# Power.net
KiCad netlist of a schematic drawn in Altium Designer
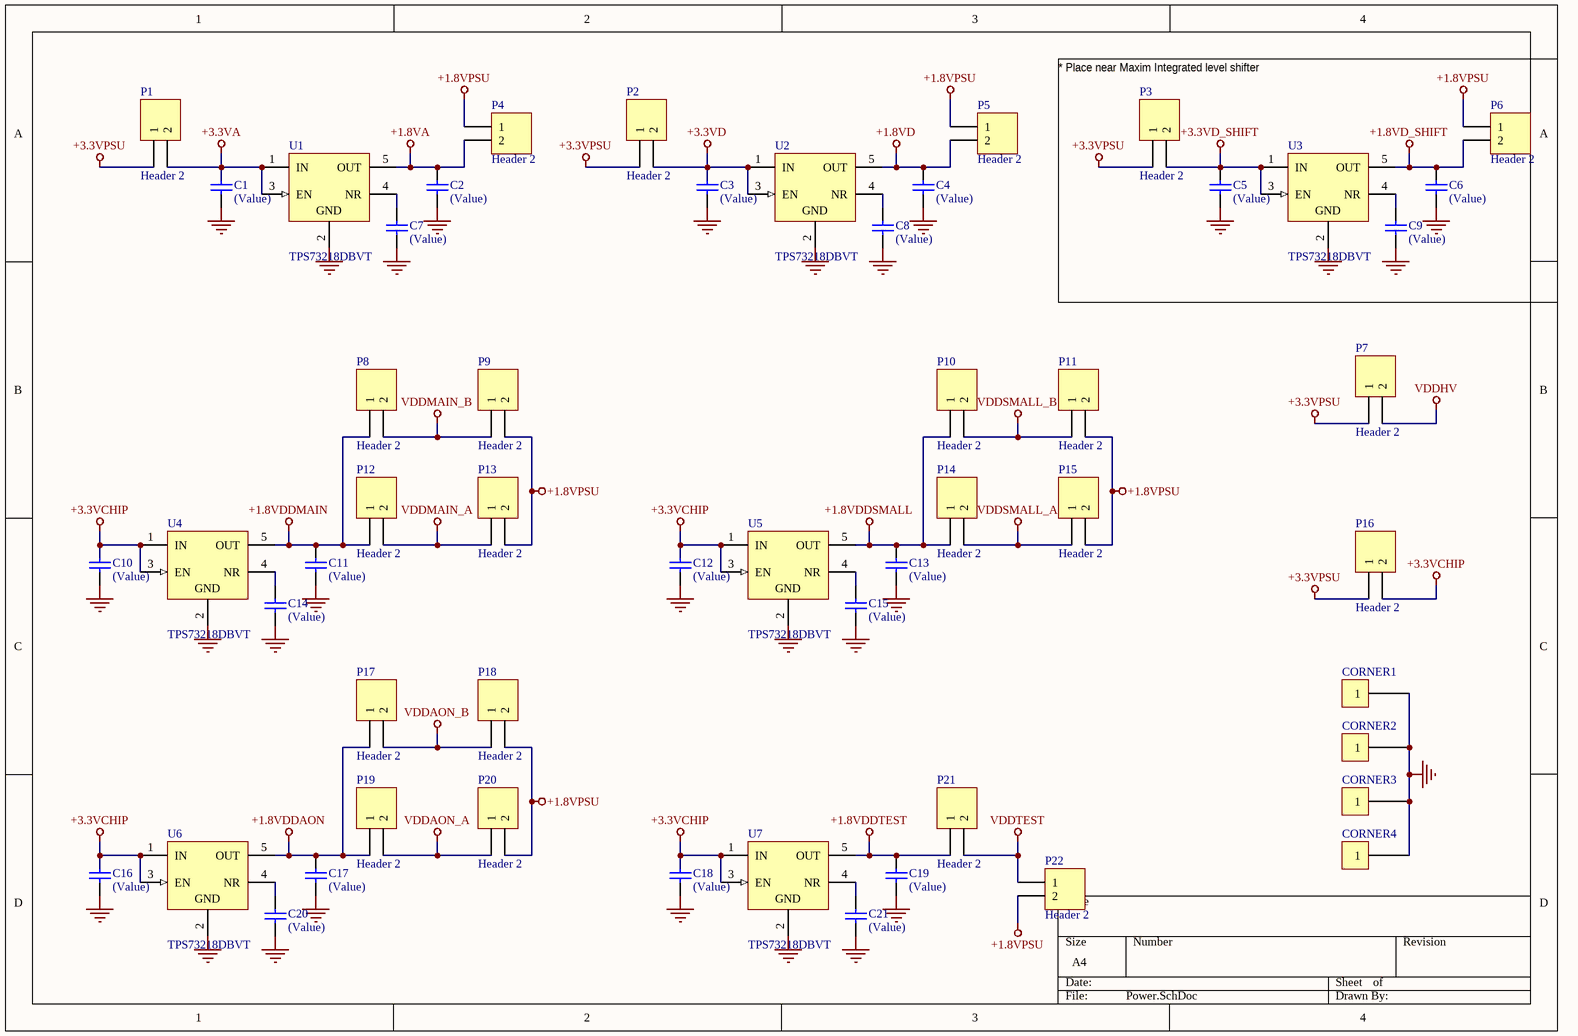
[diagram p0: Power.SchDoc]

(export (version "E")
  (design (tool "Eeschema 10.0.6"))
  (components
    (comp (ref "C1")
      (value "(Value)")
      (footprint "CAPC1608X90X35ML10T15")
      (description "0603")
      (fields (field (name "MANUFACTURER") "Murata"))
      (libsource (lib "Altium Content Vault") (part "CAP-NP-2"))
    )
    (comp (ref "C2")
      (value "(Value)")
      (footprint "CAPC1608X90X35ML10T15")
      (description "0603")
      (fields (field (name "MANUFACTURER") "Murata"))
      (libsource (lib "Altium Content Vault") (part "CAP-NP-2"))
    )
    (comp (ref "C3")
      (value "(Value)")
      (footprint "CAPC1608X90X35ML10T15")
      (description "0603")
      (fields (field (name "MANUFACTURER") "Murata"))
      (libsource (lib "Altium Content Vault") (part "CAP-NP-2"))
    )
    (comp (ref "C4")
      (value "(Value)")
      (footprint "CAPC1608X90X35ML10T15")
      (description "0603")
      (fields (field (name "MANUFACTURER") "Murata"))
      (libsource (lib "Altium Content Vault") (part "CAP-NP-2"))
    )
    (comp (ref "C5")
      (value "(Value)")
      (footprint "CAPC1608X90X35ML10T15")
      (description "0603")
      (fields (field (name "MANUFACTURER") "Murata"))
      (libsource (lib "Altium Content Vault") (part "CAP-NP-2"))
    )
    (comp (ref "C6")
      (value "(Value)")
      (footprint "CAPC1608X90X35ML10T15")
      (description "0603")
      (fields (field (name "MANUFACTURER") "Murata"))
      (libsource (lib "Altium Content Vault") (part "CAP-NP-2"))
    )
    (comp (ref "C7")
      (value "(Value)")
      (footprint "CAPC1608X90X35ML10T15")
      (description "0603")
      (fields (field (name "MANUFACTURER") "Murata"))
      (libsource (lib "Altium Content Vault") (part "CAP-NP-2"))
    )
    (comp (ref "C8")
      (value "(Value)")
      (footprint "CAPC1608X90X35ML10T15")
      (description "0603")
      (fields (field (name "MANUFACTURER") "Murata"))
      (libsource (lib "Altium Content Vault") (part "CAP-NP-2"))
    )
    (comp (ref "C9")
      (value "(Value)")
      (footprint "CAPC1608X90X35ML10T15")
      (description "0603")
      (fields (field (name "MANUFACTURER") "Murata"))
      (libsource (lib "Altium Content Vault") (part "CAP-NP-2"))
    )
    (comp (ref "C10")
      (value "(Value)")
      (footprint "CAPC1608X90X35ML10T15")
      (description "0603")
      (fields (field (name "MANUFACTURER") "Murata"))
      (libsource (lib "Altium Content Vault") (part "CAP-NP-2"))
    )
    (comp (ref "C11")
      (value "(Value)")
      (footprint "CAPC1608X90X35ML10T15")
      (description "0603")
      (fields (field (name "MANUFACTURER") "Murata"))
      (libsource (lib "Altium Content Vault") (part "CAP-NP-2"))
    )
    (comp (ref "C12")
      (value "(Value)")
      (footprint "CAPC1608X90X35ML10T15")
      (description "0603")
      (fields (field (name "MANUFACTURER") "Murata"))
      (libsource (lib "Altium Content Vault") (part "CAP-NP-2"))
    )
    (comp (ref "C13")
      (value "(Value)")
      (footprint "CAPC1608X90X35ML10T15")
      (description "0603")
      (fields (field (name "MANUFACTURER") "Murata"))
      (libsource (lib "Altium Content Vault") (part "CAP-NP-2"))
    )
    (comp (ref "C14")
      (value "(Value)")
      (footprint "CAPC1608X90X35ML10T15")
      (description "0603")
      (fields (field (name "MANUFACTURER") "Murata"))
      (libsource (lib "Altium Content Vault") (part "CAP-NP-2"))
    )
    (comp (ref "C15")
      (value "(Value)")
      (footprint "CAPC1608X90X35ML10T15")
      (description "0603")
      (fields (field (name "MANUFACTURER") "Murata"))
      (libsource (lib "Altium Content Vault") (part "CAP-NP-2"))
    )
    (comp (ref "C16")
      (value "(Value)")
      (footprint "CAPC1608X90X35ML10T15")
      (description "0603")
      (fields (field (name "MANUFACTURER") "Murata"))
      (libsource (lib "Altium Content Vault") (part "CAP-NP-2"))
    )
    (comp (ref "C17")
      (value "(Value)")
      (footprint "CAPC1608X90X35ML10T15")
      (description "0603")
      (fields (field (name "MANUFACTURER") "Murata"))
      (libsource (lib "Altium Content Vault") (part "CAP-NP-2"))
    )
    (comp (ref "C18")
      (value "(Value)")
      (footprint "CAPC1608X90X35ML10T15")
      (description "0603")
      (fields (field (name "MANUFACTURER") "Murata"))
      (libsource (lib "Altium Content Vault") (part "CAP-NP-2"))
    )
    (comp (ref "C19")
      (value "(Value)")
      (footprint "CAPC1608X90X35ML10T15")
      (description "0603")
      (fields (field (name "MANUFACTURER") "Murata"))
      (libsource (lib "Altium Content Vault") (part "CAP-NP-2"))
    )
    (comp (ref "C20")
      (value "(Value)")
      (footprint "CAPC1608X90X35ML10T15")
      (description "0603")
      (fields (field (name "MANUFACTURER") "Murata"))
      (libsource (lib "Altium Content Vault") (part "CAP-NP-2"))
    )
    (comp (ref "C21")
      (value "(Value)")
      (footprint "CAPC1608X90X35ML10T15")
      (description "0603")
      (fields (field (name "MANUFACTURER") "Murata"))
      (libsource (lib "Altium Content Vault") (part "CAP-NP-2"))
    )
    (comp (ref "CORNER1")
      (value "Corner Mount")
      (footprint "CornerMount")
      (libsource (lib "intlib") (part "Corner Mount"))
    )
    (comp (ref "CORNER2")
      (value "Corner Mount")
      (footprint "CornerMount")
      (libsource (lib "intlib") (part "Corner Mount"))
    )
    (comp (ref "CORNER3")
      (value "Corner Mount")
      (footprint "CornerMount")
      (libsource (lib "intlib") (part "Corner Mount"))
    )
    (comp (ref "CORNER4")
      (value "Corner Mount")
      (footprint "CornerMount")
      (libsource (lib "intlib") (part "Corner Mount"))
    )
    (comp (ref "P1")
      (value "Header 2")
      (footprint "HDR1X2")
      (description "Header, 2-Pin")
      (fields (field (name "PUBLISHER") "Altium Limited"))
      (libsource (lib "") (part "Header 2_1"))
    )
    (comp (ref "P2")
      (value "Header 2")
      (footprint "HDR1X2")
      (description "Header, 2-Pin")
      (fields (field (name "PUBLISHER") "Altium Limited"))
      (libsource (lib "") (part "Header 2_1"))
    )
    (comp (ref "P3")
      (value "Header 2")
      (footprint "HDR1X2")
      (description "Header, 2-Pin")
      (fields (field (name "PUBLISHER") "Altium Limited"))
      (libsource (lib "") (part "Header 2_1"))
    )
    (comp (ref "P4")
      (value "Header 2")
      (footprint "HDR1X2")
      (description "Header, 2-Pin")
      (fields (field (name "PUBLISHER") "Altium Limited"))
      (libsource (lib "Miscellaneous Connectors") (part "Header 2"))
    )
    (comp (ref "P5")
      (value "Header 2")
      (footprint "HDR1X2")
      (description "Header, 2-Pin")
      (fields (field (name "PUBLISHER") "Altium Limited"))
      (libsource (lib "Miscellaneous Connectors") (part "Header 2"))
    )
    (comp (ref "P6")
      (value "Header 2")
      (footprint "HDR1X2")
      (description "Header, 2-Pin")
      (fields (field (name "PUBLISHER") "Altium Limited"))
      (libsource (lib "Miscellaneous Connectors") (part "Header 2"))
    )
    (comp (ref "P7")
      (value "Header 2")
      (footprint "HDR1X2")
      (description "Header, 2-Pin")
      (fields (field (name "PUBLISHER") "Altium Limited"))
      (libsource (lib "") (part "Header 2_1"))
    )
    (comp (ref "P8")
      (value "Header 2")
      (footprint "HDR1X2")
      (description "Header, 2-Pin")
      (fields (field (name "PUBLISHER") "Altium Limited"))
      (libsource (lib "") (part "Header 2_1"))
    )
    (comp (ref "P9")
      (value "Header 2")
      (footprint "HDR1X2")
      (description "Header, 2-Pin")
      (fields (field (name "PUBLISHER") "Altium Limited"))
      (libsource (lib "") (part "Header 2_1"))
    )
    (comp (ref "P10")
      (value "Header 2")
      (footprint "HDR1X2")
      (description "Header, 2-Pin")
      (fields (field (name "PUBLISHER") "Altium Limited"))
      (libsource (lib "") (part "Header 2_1"))
    )
    (comp (ref "P11")
      (value "Header 2")
      (footprint "HDR1X2")
      (description "Header, 2-Pin")
      (fields (field (name "PUBLISHER") "Altium Limited"))
      (libsource (lib "") (part "Header 2_1"))
    )
    (comp (ref "P12")
      (value "Header 2")
      (footprint "HDR1X2")
      (description "Header, 2-Pin")
      (fields (field (name "PUBLISHER") "Altium Limited"))
      (libsource (lib "") (part "Header 2_1"))
    )
    (comp (ref "P13")
      (value "Header 2")
      (footprint "HDR1X2")
      (description "Header, 2-Pin")
      (fields (field (name "PUBLISHER") "Altium Limited"))
      (libsource (lib "") (part "Header 2_1"))
    )
    (comp (ref "P14")
      (value "Header 2")
      (footprint "HDR1X2")
      (description "Header, 2-Pin")
      (fields (field (name "PUBLISHER") "Altium Limited"))
      (libsource (lib "") (part "Header 2_1"))
    )
    (comp (ref "P15")
      (value "Header 2")
      (footprint "HDR1X2")
      (description "Header, 2-Pin")
      (fields (field (name "PUBLISHER") "Altium Limited"))
      (libsource (lib "") (part "Header 2_1"))
    )
    (comp (ref "P16")
      (value "Header 2")
      (footprint "HDR1X2")
      (description "Header, 2-Pin")
      (fields (field (name "PUBLISHER") "Altium Limited"))
      (libsource (lib "") (part "Header 2_1"))
    )
    (comp (ref "P17")
      (value "Header 2")
      (footprint "HDR1X2")
      (description "Header, 2-Pin")
      (fields (field (name "PUBLISHER") "Altium Limited"))
      (libsource (lib "") (part "Header 2_1"))
    )
    (comp (ref "P18")
      (value "Header 2")
      (footprint "HDR1X2")
      (description "Header, 2-Pin")
      (fields (field (name "PUBLISHER") "Altium Limited"))
      (libsource (lib "") (part "Header 2_1"))
    )
    (comp (ref "P19")
      (value "Header 2")
      (footprint "HDR1X2")
      (description "Header, 2-Pin")
      (fields (field (name "PUBLISHER") "Altium Limited"))
      (libsource (lib "") (part "Header 2_1"))
    )
    (comp (ref "P20")
      (value "Header 2")
      (footprint "HDR1X2")
      (description "Header, 2-Pin")
      (fields (field (name "PUBLISHER") "Altium Limited"))
      (libsource (lib "") (part "Header 2_1"))
    )
    (comp (ref "P21")
      (value "Header 2")
      (footprint "HDR1X2")
      (description "Header, 2-Pin")
      (fields (field (name "PUBLISHER") "Altium Limited"))
      (libsource (lib "") (part "Header 2_1"))
    )
    (comp (ref "P22")
      (value "Header 2")
      (footprint "HDR1X2")
      (description "Header, 2-Pin")
      (fields (field (name "PUBLISHER") "Altium Limited"))
      (libsource (lib "Miscellaneous Connectors") (part "Header 2"))
    )
    (comp (ref "U1")
      (value "TPS73218DBVT")
      (footprint "DBV0005A_N")
      (fields (field (name "MANUFACTURER") "Texas Instruments"))
      (libsource (lib "Altium Content Vault") (part "TI-TPS79NXX-YYSOT5"))
    )
    (comp (ref "U2")
      (value "TPS73218DBVT")
      (footprint "DBV0005A_N")
      (fields (field (name "MANUFACTURER") "Texas Instruments"))
      (libsource (lib "Altium Content Vault") (part "TI-TPS79NXX-YYSOT5"))
    )
    (comp (ref "U3")
      (value "TPS73218DBVT")
      (footprint "DBV0005A_N")
      (fields (field (name "MANUFACTURER") "Texas Instruments"))
      (libsource (lib "Altium Content Vault") (part "TI-TPS79NXX-YYSOT5"))
    )
    (comp (ref "U4")
      (value "TPS73218DBVT")
      (footprint "DBV0005A_N")
      (fields (field (name "MANUFACTURER") "Texas Instruments"))
      (libsource (lib "Altium Content Vault") (part "TI-TPS79NXX-YYSOT5"))
    )
    (comp (ref "U5")
      (value "TPS73218DBVT")
      (footprint "DBV0005A_N")
      (fields (field (name "MANUFACTURER") "Texas Instruments"))
      (libsource (lib "Altium Content Vault") (part "TI-TPS79NXX-YYSOT5"))
    )
    (comp (ref "U6")
      (value "TPS73218DBVT")
      (footprint "DBV0005A_N")
      (fields (field (name "MANUFACTURER") "Texas Instruments"))
      (libsource (lib "Altium Content Vault") (part "TI-TPS79NXX-YYSOT5"))
    )
    (comp (ref "U7")
      (value "TPS73218DBVT")
      (footprint "DBV0005A_N")
      (fields (field (name "MANUFACTURER") "Texas Instruments"))
      (libsource (lib "Altium Content Vault") (part "TI-TPS79NXX-YYSOT5"))
    )
  )
  (nets
    (net (code "1") (name "+1.8VA") (class "Default")
      (node (ref "C2") (pin "1") (pinfunction "1_1") (pintype "passive"))
      (node (ref "P4") (pin "2") (pinfunction "2_2") (pintype "passive"))
      (node (ref "U1") (pin "5") (pinfunction "OUT_5") (pintype "power_in"))
    )
    (net (code "2") (name "+1.8VD") (class "Default")
      (node (ref "C4") (pin "1") (pinfunction "1_1") (pintype "passive"))
      (node (ref "P5") (pin "2") (pinfunction "2_2") (pintype "passive"))
      (node (ref "U2") (pin "5") (pinfunction "OUT_5") (pintype "power_in"))
    )
    (net (code "3") (name "+1.8VDDAON") (class "Default")
      (node (ref "C17") (pin "1") (pinfunction "1_1") (pintype "passive"))
      (node (ref "P17") (pin "1") (pinfunction "1_1") (pintype "passive"))
      (node (ref "P19") (pin "1") (pinfunction "1_1") (pintype "passive"))
      (node (ref "U6") (pin "5") (pinfunction "OUT_5") (pintype "power_in"))
    )
    (net (code "4") (name "+1.8VDDMAIN") (class "Default")
      (node (ref "C11") (pin "1") (pinfunction "1_1") (pintype "passive"))
      (node (ref "P12") (pin "1") (pinfunction "1_1") (pintype "passive"))
      (node (ref "P8") (pin "1") (pinfunction "1_1") (pintype "passive"))
      (node (ref "U4") (pin "5") (pinfunction "OUT_5") (pintype "power_in"))
    )
    (net (code "5") (name "+1.8VDDSMALL") (class "Default")
      (node (ref "C13") (pin "1") (pinfunction "1_1") (pintype "passive"))
      (node (ref "P10") (pin "1") (pinfunction "1_1") (pintype "passive"))
      (node (ref "P14") (pin "1") (pinfunction "1_1") (pintype "passive"))
      (node (ref "U5") (pin "5") (pinfunction "OUT_5") (pintype "power_in"))
    )
    (net (code "6") (name "+1.8VDDTEST") (class "Default")
      (node (ref "C19") (pin "1") (pinfunction "1_1") (pintype "passive"))
      (node (ref "P21") (pin "1") (pinfunction "1_1") (pintype "passive"))
      (node (ref "U7") (pin "5") (pinfunction "OUT_5") (pintype "power_in"))
    )
    (net (code "7") (name "+1.8VD_SHIFT") (class "Default")
      (node (ref "C6") (pin "1") (pinfunction "1_1") (pintype "passive"))
      (node (ref "P6") (pin "2") (pinfunction "2_2") (pintype "passive"))
      (node (ref "U3") (pin "5") (pinfunction "OUT_5") (pintype "power_in"))
    )
    (net (code "8") (name "+1.8VPSU") (class "Default")
      (node (ref "P11") (pin "2") (pinfunction "2_2") (pintype "passive"))
      (node (ref "P13") (pin "2") (pinfunction "2_2") (pintype "passive"))
      (node (ref "P15") (pin "2") (pinfunction "2_2") (pintype "passive"))
      (node (ref "P18") (pin "2") (pinfunction "2_2") (pintype "passive"))
      (node (ref "P20") (pin "2") (pinfunction "2_2") (pintype "passive"))
      (node (ref "P22") (pin "2") (pinfunction "2_2") (pintype "passive"))
      (node (ref "P4") (pin "1") (pinfunction "1_1") (pintype "passive"))
      (node (ref "P5") (pin "1") (pinfunction "1_1") (pintype "passive"))
      (node (ref "P6") (pin "1") (pinfunction "1_1") (pintype "passive"))
      (node (ref "P9") (pin "2") (pinfunction "2_2") (pintype "passive"))
    )
    (net (code "9") (name "+3.3VA") (class "Default")
      (node (ref "C1") (pin "1") (pinfunction "1_1") (pintype "passive"))
      (node (ref "P1") (pin "2") (pinfunction "2_2") (pintype "passive"))
      (node (ref "U1") (pin "1") (pinfunction "IN_1") (pintype "power_in"))
      (node (ref "U1") (pin "3") (pinfunction "EN_3") (pintype "input"))
    )
    (net (code "10") (name "+3.3VCHIP") (class "Default")
      (node (ref "C10") (pin "1") (pinfunction "1_1") (pintype "passive"))
      (node (ref "C12") (pin "1") (pinfunction "1_1") (pintype "passive"))
      (node (ref "C16") (pin "1") (pinfunction "1_1") (pintype "passive"))
      (node (ref "C18") (pin "1") (pinfunction "1_1") (pintype "passive"))
      (node (ref "P16") (pin "2") (pinfunction "2_2") (pintype "passive"))
      (node (ref "U4") (pin "1") (pinfunction "IN_1") (pintype "power_in"))
      (node (ref "U4") (pin "3") (pinfunction "EN_3") (pintype "input"))
      (node (ref "U5") (pin "1") (pinfunction "IN_1") (pintype "power_in"))
      (node (ref "U5") (pin "3") (pinfunction "EN_3") (pintype "input"))
      (node (ref "U6") (pin "1") (pinfunction "IN_1") (pintype "power_in"))
      (node (ref "U6") (pin "3") (pinfunction "EN_3") (pintype "input"))
      (node (ref "U7") (pin "1") (pinfunction "IN_1") (pintype "power_in"))
      (node (ref "U7") (pin "3") (pinfunction "EN_3") (pintype "input"))
    )
    (net (code "11") (name "+3.3VD") (class "Default")
      (node (ref "C3") (pin "1") (pinfunction "1_1") (pintype "passive"))
      (node (ref "P2") (pin "2") (pinfunction "2_2") (pintype "passive"))
      (node (ref "U2") (pin "1") (pinfunction "IN_1") (pintype "power_in"))
      (node (ref "U2") (pin "3") (pinfunction "EN_3") (pintype "input"))
    )
    (net (code "12") (name "+3.3VD_SHIFT") (class "Default")
      (node (ref "C5") (pin "1") (pinfunction "1_1") (pintype "passive"))
      (node (ref "P3") (pin "2") (pinfunction "2_2") (pintype "passive"))
      (node (ref "U3") (pin "1") (pinfunction "IN_1") (pintype "power_in"))
      (node (ref "U3") (pin "3") (pinfunction "EN_3") (pintype "input"))
    )
    (net (code "13") (name "+3.3VPSU") (class "Default")
      (node (ref "P1") (pin "1") (pinfunction "1_1") (pintype "passive"))
      (node (ref "P16") (pin "1") (pinfunction "1_1") (pintype "passive"))
      (node (ref "P2") (pin "1") (pinfunction "1_1") (pintype "passive"))
      (node (ref "P3") (pin "1") (pinfunction "1_1") (pintype "passive"))
      (node (ref "P7") (pin "1") (pinfunction "1_1") (pintype "passive"))
    )
    (net (code "14") (name "GND") (class "Default")
      (node (ref "C1") (pin "2") (pinfunction "2_2") (pintype "passive"))
      (node (ref "C10") (pin "2") (pinfunction "2_2") (pintype "passive"))
      (node (ref "C11") (pin "2") (pinfunction "2_2") (pintype "passive"))
      (node (ref "C12") (pin "2") (pinfunction "2_2") (pintype "passive"))
      (node (ref "C13") (pin "2") (pinfunction "2_2") (pintype "passive"))
      (node (ref "C14") (pin "2") (pinfunction "2_2") (pintype "passive"))
      (node (ref "C15") (pin "2") (pinfunction "2_2") (pintype "passive"))
      (node (ref "C16") (pin "2") (pinfunction "2_2") (pintype "passive"))
      (node (ref "C17") (pin "2") (pinfunction "2_2") (pintype "passive"))
      (node (ref "C18") (pin "2") (pinfunction "2_2") (pintype "passive"))
      (node (ref "C19") (pin "2") (pinfunction "2_2") (pintype "passive"))
      (node (ref "C2") (pin "2") (pinfunction "2_2") (pintype "passive"))
      (node (ref "C20") (pin "2") (pinfunction "2_2") (pintype "passive"))
      (node (ref "C21") (pin "2") (pinfunction "2_2") (pintype "passive"))
      (node (ref "C3") (pin "2") (pinfunction "2_2") (pintype "passive"))
      (node (ref "C4") (pin "2") (pinfunction "2_2") (pintype "passive"))
      (node (ref "C5") (pin "2") (pinfunction "2_2") (pintype "passive"))
      (node (ref "C6") (pin "2") (pinfunction "2_2") (pintype "passive"))
      (node (ref "C7") (pin "2") (pinfunction "2_2") (pintype "passive"))
      (node (ref "C8") (pin "2") (pinfunction "2_2") (pintype "passive"))
      (node (ref "C9") (pin "2") (pinfunction "2_2") (pintype "passive"))
      (node (ref "CORNER1") (pin "1") (pinfunction "1_1") (pintype "passive"))
      (node (ref "CORNER2") (pin "1") (pinfunction "1_1") (pintype "passive"))
      (node (ref "CORNER3") (pin "1") (pinfunction "1_1") (pintype "passive"))
      (node (ref "CORNER4") (pin "1") (pinfunction "1_1") (pintype "passive"))
      (node (ref "U1") (pin "2") (pinfunction "GND_2") (pintype "power_in"))
      (node (ref "U2") (pin "2") (pinfunction "GND_2") (pintype "power_in"))
      (node (ref "U3") (pin "2") (pinfunction "GND_2") (pintype "power_in"))
      (node (ref "U4") (pin "2") (pinfunction "GND_2") (pintype "power_in"))
      (node (ref "U5") (pin "2") (pinfunction "GND_2") (pintype "power_in"))
      (node (ref "U6") (pin "2") (pinfunction "GND_2") (pintype "power_in"))
      (node (ref "U7") (pin "2") (pinfunction "GND_2") (pintype "power_in"))
    )
    (net (code "15") (name "Net-(U1-NR)") (class "Default")
      (node (ref "C7") (pin "1") (pinfunction "1_1") (pintype "passive"))
      (node (ref "U1") (pin "4") (pinfunction "NR_4") (pintype "passive"))
    )
    (net (code "16") (name "Net-(U2-NR)") (class "Default")
      (node (ref "C8") (pin "1") (pinfunction "1_1") (pintype "passive"))
      (node (ref "U2") (pin "4") (pinfunction "NR_4") (pintype "passive"))
    )
    (net (code "17") (name "Net-(U3-NR)") (class "Default")
      (node (ref "C9") (pin "1") (pinfunction "1_1") (pintype "passive"))
      (node (ref "U3") (pin "4") (pinfunction "NR_4") (pintype "passive"))
    )
    (net (code "18") (name "Net-(U4-NR)") (class "Default")
      (node (ref "C14") (pin "1") (pinfunction "1_1") (pintype "passive"))
      (node (ref "U4") (pin "4") (pinfunction "NR_4") (pintype "passive"))
    )
    (net (code "19") (name "Net-(U5-NR)") (class "Default")
      (node (ref "C15") (pin "1") (pinfunction "1_1") (pintype "passive"))
      (node (ref "U5") (pin "4") (pinfunction "NR_4") (pintype "passive"))
    )
    (net (code "20") (name "Net-(U6-NR)") (class "Default")
      (node (ref "C20") (pin "1") (pinfunction "1_1") (pintype "passive"))
      (node (ref "U6") (pin "4") (pinfunction "NR_4") (pintype "passive"))
    )
    (net (code "21") (name "Net-(U7-NR)") (class "Default")
      (node (ref "C21") (pin "1") (pinfunction "1_1") (pintype "passive"))
      (node (ref "U7") (pin "4") (pinfunction "NR_4") (pintype "passive"))
    )
    (net (code "22") (name "VDDAON_A") (class "Default")
      (node (ref "P19") (pin "2") (pinfunction "2_2") (pintype "passive"))
      (node (ref "P20") (pin "1") (pinfunction "1_1") (pintype "passive"))
    )
    (net (code "23") (name "VDDAON_B") (class "Default")
      (node (ref "P17") (pin "2") (pinfunction "2_2") (pintype "passive"))
      (node (ref "P18") (pin "1") (pinfunction "1_1") (pintype "passive"))
    )
    (net (code "24") (name "VDDHV") (class "Default")
      (node (ref "P7") (pin "2") (pinfunction "2_2") (pintype "passive"))
    )
    (net (code "25") (name "VDDMAIN_A") (class "Default")
      (node (ref "P12") (pin "2") (pinfunction "2_2") (pintype "passive"))
      (node (ref "P13") (pin "1") (pinfunction "1_1") (pintype "passive"))
    )
    (net (code "26") (name "VDDMAIN_B") (class "Default")
      (node (ref "P8") (pin "2") (pinfunction "2_2") (pintype "passive"))
      (node (ref "P9") (pin "1") (pinfunction "1_1") (pintype "passive"))
    )
    (net (code "27") (name "VDDSMALL_A") (class "Default")
      (node (ref "P14") (pin "2") (pinfunction "2_2") (pintype "passive"))
      (node (ref "P15") (pin "1") (pinfunction "1_1") (pintype "passive"))
    )
    (net (code "28") (name "VDDSMALL_B") (class "Default")
      (node (ref "P10") (pin "2") (pinfunction "2_2") (pintype "passive"))
      (node (ref "P11") (pin "1") (pinfunction "1_1") (pintype "passive"))
    )
    (net (code "29") (name "VDDTEST") (class "Default")
      (node (ref "P21") (pin "2") (pinfunction "2_2") (pintype "passive"))
      (node (ref "P22") (pin "1") (pinfunction "1_1") (pintype "passive"))
    )
  )
)
